# design.net
KiCad netlist of a schematic drawn in Altium Designer
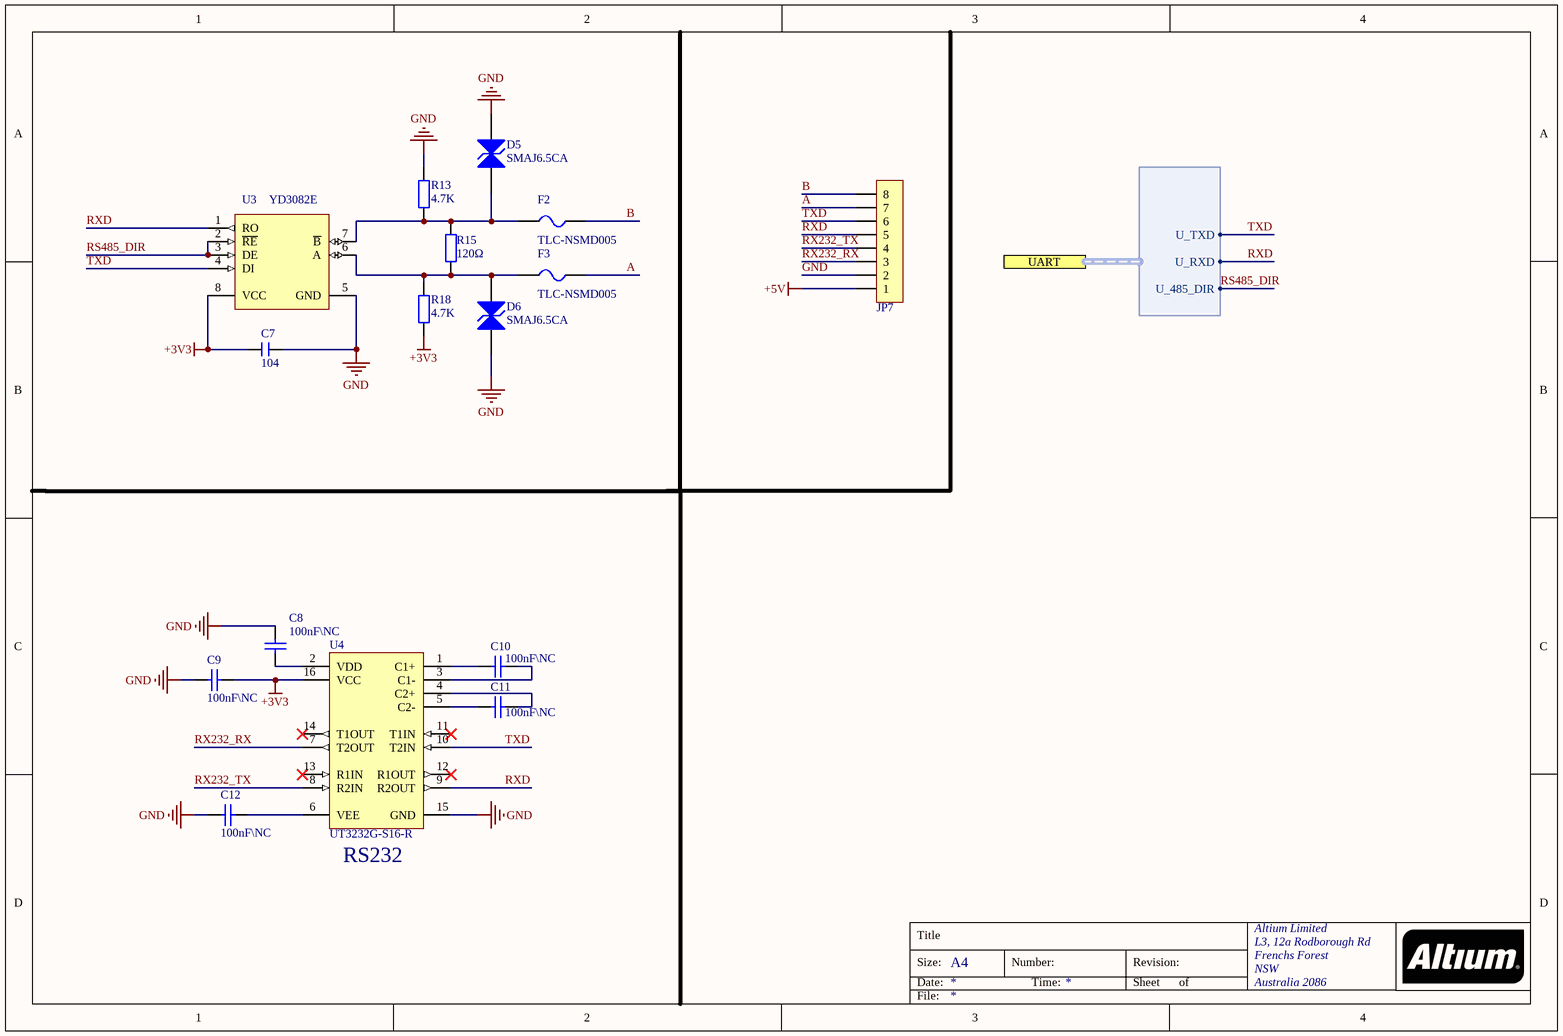
[diagram p0: 通信接口.SchDoc]

(export (version "E")
  (design (tool "Eeschema 10.0.6"))
  (components
    (comp (ref "C7")
      (value "104")
      (footprint "C 0603")
      (description "无极性贴片电容")
      (fields (field (name "版权归属") "源创客"))
      (libsource (lib "源创客") (part "C"))
    )
    (comp (ref "C8")
      (value "100n~{F}NC")
      (footprint "0603_C")
      (description "贴片电容")
      (libsource (lib "Miscellaneous Devices LC") (part "0603 100nF (104) 10% 50V"))
    )
    (comp (ref "C9")
      (value "100n~{F}NC")
      (footprint "0603_C")
      (description "贴片电容")
      (libsource (lib "Miscellaneous Devices LC") (part "0603 100nF (104) 10% 50V"))
    )
    (comp (ref "C10")
      (value "100n~{F}NC")
      (footprint "0603_C")
      (description "贴片电容")
      (libsource (lib "Miscellaneous Devices LC") (part "0603 100nF (104) 10% 50V"))
    )
    (comp (ref "C11")
      (value "100n~{F}NC")
      (footprint "0603_C")
      (description "贴片电容")
      (libsource (lib "Miscellaneous Devices LC") (part "0603 100nF (104) 10% 50V"))
    )
    (comp (ref "C12")
      (value "100n~{F}NC")
      (footprint "0603_C")
      (description "贴片电容")
      (libsource (lib "Miscellaneous Devices LC") (part "0603 100nF (104) 10% 50V"))
    )
    (comp (ref "D5")
      (value "SMAJ6.5CA")
      (footprint "SMA(DO-214AC)_S1")
      (description "TVS")
      (libsource (lib "Miscellaneous Devices LC") (part "SMB/DO-214AA P6SMB6.8CA"))
    )
    (comp (ref "D6")
      (value "SMAJ6.5CA")
      (footprint "SMA(DO-214AC)_S1")
      (description "TVS")
      (libsource (lib "Miscellaneous Devices LC") (part "SMB/DO-214AA P6SMB6.8CA"))
    )
    (comp (ref "F2")
      (value "TLC-NSMD005")
      (footprint "FU 1206")
      (description "贴片保险丝")
      (fields (field (name "版权归属") "源创客"))
      (libsource (lib "源创客") (part "FU"))
    )
    (comp (ref "F3")
      (value "TLC-NSMD005")
      (footprint "FU 1206")
      (description "贴片保险丝")
      (fields (field (name "版权归属") "源创客"))
      (libsource (lib "源创客") (part "FU"))
    )
    (comp (ref "JP7")
      (value "XH-2.54-8P")
      (footprint "XH2.54-8P")
      (description "8P接插件")
      (fields (field (name "版权归属") "源创客"))
      (libsource (lib "源创客") (part "Header 8"))
    )
    (comp (ref "R13")
      (value "4.7K")
      (footprint "R 0603")
      (description "贴片电阻")
      (fields (field (name "版权归属") "源创客"))
      (libsource (lib "源创客") (part "R"))
    )
    (comp (ref "R15")
      (value "120Ω")
      (footprint "0603_R")
      (description "贴片电阻")
      (libsource (lib "Miscellaneous Devices LC") (part "0603 120Ω (1200) 1%"))
    )
    (comp (ref "R18")
      (value "4.7K")
      (footprint "R 0603")
      (description "贴片电阻")
      (fields (field (name "版权归属") "源创客"))
      (libsource (lib "源创客") (part "R"))
    )
    (comp (ref "U3")
      (value "YD3082E")
      (footprint "SOIC-8_150mil")
      (description "RS-485/RS-422")
      (libsource (lib "Miscellaneous Devices LC") (part "SP485EEN-L/TR"))
    )
    (comp (ref "U4")
      (value "UT3232G-S16-R")
      (footprint "SOIC-16_150mil")
      (description "RS232")
      (libsource (lib "Miscellaneous Devices LC") (part "MAX232ESE"))
    )
  )
  (nets
    (net (code "2") (name "+3V3") (class "Default")
      (node (ref "C7") (pin "1") (pinfunction "1_1") (pintype "passive"))
      (node (ref "C9") (pin "2") (pinfunction "2_2") (pintype "passive"))
      (node (ref "R18") (pin "1") (pinfunction "1_1") (pintype "passive"))
      (node (ref "U3") (pin "8") (pinfunction "VCC_8") (pintype "power_in"))
      (node (ref "U4") (pin "16") (pinfunction "VCC_16") (pintype "power_in"))
    )
    (net (code "3") (name "+5V") (class "Default")
      (node (ref "JP7") (pin "1") (pinfunction "1_1") (pintype "passive"))
    )
    (net (code "4") (name "/A") (class "Default")
      (node (ref "F3") (pin "2") (pinfunction "2_2") (pintype "passive"))
      (node (ref "JP7") (pin "7") (pinfunction "7_7") (pintype "passive"))
    )
    (net (code "5") (name "/B") (class "Default")
      (node (ref "F2") (pin "2") (pinfunction "2_2") (pintype "passive"))
      (node (ref "JP7") (pin "8") (pinfunction "8_8") (pintype "passive"))
    )
    (net (code "6") (name "/RS485_DIR") (class "Default")
      (node (ref "U3") (pin "2") (pinfunction "~{RE}_2") (pintype "input"))
      (node (ref "U3") (pin "3") (pinfunction "DE_3") (pintype "input"))
    )
    (net (code "7") (name "/RX232_RX") (class "Default")
      (node (ref "JP7") (pin "3") (pinfunction "3_3") (pintype "passive"))
      (node (ref "U4") (pin "7") (pinfunction "T2OUT_7") (pintype "output"))
    )
    (net (code "8") (name "/RX232_TX") (class "Default")
      (node (ref "JP7") (pin "4") (pinfunction "4_4") (pintype "passive"))
      (node (ref "U4") (pin "8") (pinfunction "R2IN_8") (pintype "input"))
    )
    (net (code "9") (name "/RXD") (class "Default")
      (node (ref "JP7") (pin "5") (pinfunction "5_5") (pintype "passive"))
      (node (ref "U3") (pin "1") (pinfunction "RO_1") (pintype "output"))
      (node (ref "U4") (pin "9") (pinfunction "R2OUT_9") (pintype "output"))
    )
    (net (code "10") (name "/TXD") (class "Default")
      (node (ref "JP7") (pin "6") (pinfunction "6_6") (pintype "passive"))
      (node (ref "U3") (pin "4") (pinfunction "DI_4") (pintype "input"))
      (node (ref "U4") (pin "10") (pinfunction "T2IN_10") (pintype "input"))
    )
    (net (code "12") (name "GND") (class "Default")
      (node (ref "C12") (pin "1") (pinfunction "1_1") (pintype "passive"))
      (node (ref "C7") (pin "2") (pinfunction "2_2") (pintype "passive"))
      (node (ref "C8") (pin "2") (pinfunction "2_2") (pintype "passive"))
      (node (ref "C9") (pin "1") (pinfunction "1_1") (pintype "passive"))
      (node (ref "D5") (pin "1") (pinfunction "A_1") (pintype "passive"))
      (node (ref "D6") (pin "1") (pinfunction "A_1") (pintype "passive"))
      (node (ref "JP7") (pin "2") (pinfunction "2_2") (pintype "passive"))
      (node (ref "R13") (pin "2") (pinfunction "2_2") (pintype "passive"))
      (node (ref "U3") (pin "5") (pinfunction "GND_5") (pintype "power_in"))
      (node (ref "U4") (pin "15") (pinfunction "GND_15") (pintype "power_in"))
    )
    (net (code "13") (name "Net-(D5-K)") (class "Default")
      (node (ref "D5") (pin "2") (pinfunction "K_2") (pintype "passive"))
      (node (ref "F2") (pin "1") (pinfunction "1_1") (pintype "passive"))
      (node (ref "R13") (pin "1") (pinfunction "1_1") (pintype "passive"))
      (node (ref "R15") (pin "1") (pinfunction "1_1") (pintype "passive"))
      (node (ref "U3") (pin "7") (pinfunction "~{B}_7") (pintype "bidirectional"))
    )
    (net (code "14") (name "Net-(D6-K)") (class "Default")
      (node (ref "D6") (pin "2") (pinfunction "K_2") (pintype "passive"))
      (node (ref "F3") (pin "1") (pinfunction "1_1") (pintype "passive"))
      (node (ref "R15") (pin "2") (pinfunction "2_2") (pintype "passive"))
      (node (ref "R18") (pin "2") (pinfunction "2_2") (pintype "passive"))
      (node (ref "U3") (pin "6") (pinfunction "A_6") (pintype "bidirectional"))
    )
    (net (code "15") (name "Net-(U4-C1+)") (class "Default")
      (node (ref "C10") (pin "1") (pinfunction "1_1") (pintype "passive"))
      (node (ref "U4") (pin "1") (pinfunction "C1+_1") (pintype "passive"))
    )
    (net (code "16") (name "Net-(U4-C1-)") (class "Default")
      (node (ref "C10") (pin "2") (pinfunction "2_2") (pintype "passive"))
      (node (ref "U4") (pin "3") (pinfunction "C1-_3") (pintype "passive"))
    )
    (net (code "17") (name "Net-(U4-C2+)") (class "Default")
      (node (ref "C11") (pin "2") (pinfunction "2_2") (pintype "passive"))
      (node (ref "U4") (pin "4") (pinfunction "C2+_4") (pintype "passive"))
    )
    (net (code "18") (name "Net-(U4-C2-)") (class "Default")
      (node (ref "C11") (pin "1") (pinfunction "1_1") (pintype "passive"))
      (node (ref "U4") (pin "5") (pinfunction "C2-_5") (pintype "passive"))
    )
    (net (code "19") (name "Net-(U4-VDD)") (class "Default")
      (node (ref "C8") (pin "1") (pinfunction "1_1") (pintype "passive"))
      (node (ref "U4") (pin "2") (pinfunction "VDD_2") (pintype "power_in"))
    )
    (net (code "20") (name "Net-(U4-VEE)") (class "Default")
      (node (ref "C12") (pin "2") (pinfunction "2_2") (pintype "passive"))
      (node (ref "U4") (pin "6") (pinfunction "VEE_6") (pintype "power_in"))
    )
    (net (code "21") (name "unconnected-(U4-R1IN-Pad13)") (class "Default")
      (node (ref "U4") (pin "13") (pinfunction "R1IN_13") (pintype "input+no_connect"))
    )
    (net (code "22") (name "unconnected-(U4-R1OUT-Pad12)") (class "Default")
      (node (ref "U4") (pin "12") (pinfunction "R1OUT_12") (pintype "output+no_connect"))
    )
    (net (code "23") (name "unconnected-(U4-T1IN-Pad11)") (class "Default")
      (node (ref "U4") (pin "11") (pinfunction "T1IN_11") (pintype "input+no_connect"))
    )
    (net (code "24") (name "unconnected-(U4-T1OUT-Pad14)") (class "Default")
      (node (ref "U4") (pin "14") (pinfunction "T1OUT_14") (pintype "output+no_connect"))
    )
  )
)
